# CAN.net
KiCad netlist of a schematic drawn in Altium Designer
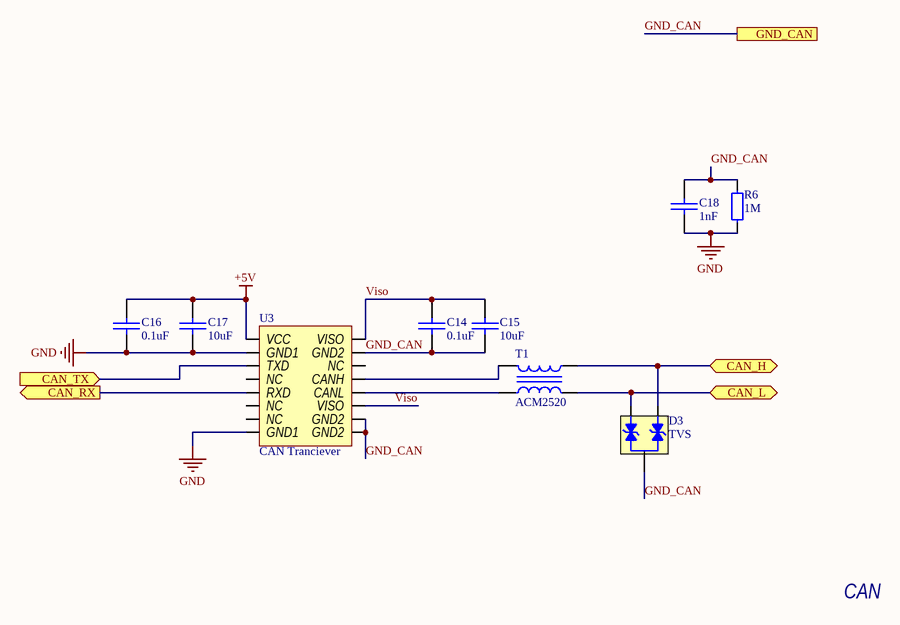
[diagram p0: CAN.SchDoc]

(export (version "E")
  (design (tool "Eeschema 10.0.6"))
  (components
    (comp (ref "C14")
      (value "0.1uF")
      (footprint "0603 Capicator")
      (description "0.1uF X7R 16V 10% 0603")
      (fields
        (field (name "MANUFACTURER") "Murata Manufacturing")
        (field (name "PART NUMBER") "GRM188R71C104KA01D")
      )
      (libsource (lib "ИРА") (part "Cap 0.1uF (0603)"))
    )
    (comp (ref "C15")
      (value "10uF")
      (footprint "0603 Capicator")
      (description "10uF X5R 25V 20% 0603")
      (fields
        (field (name "MANUFACTURER") "Murata Manufacturing")
        (field (name "PART NUMBER") "GRM188R61E106M")
      )
      (libsource (lib "ИРА") (part "Cap 10uF (0603)"))
    )
    (comp (ref "C16")
      (value "0.1uF")
      (footprint "0603 Capicator")
      (description "0.1uF X7R 16V 10% 0603")
      (fields
        (field (name "MANUFACTURER") "Murata Manufacturing")
        (field (name "PART NUMBER") "GRM188R71C104KA01D")
      )
      (libsource (lib "ИРА") (part "Cap 0.1uF (0603)"))
    )
    (comp (ref "C17")
      (value "10uF")
      (footprint "0603 Capicator")
      (description "10uF X5R 25V 20% 0603")
      (fields
        (field (name "MANUFACTURER") "Murata Manufacturing")
        (field (name "PART NUMBER") "GRM188R61E106M")
      )
      (libsource (lib "ИРА") (part "Cap 10uF (0603)"))
    )
    (comp (ref "C18")
      (value "1nF")
      (footprint "0603 Capicator")
      (description "X7R 1nF 100V 10% 0603")
      (fields
        (field (name "MANUFACTURER") "Murata Manufacturing")
        (field (name "PART NUMBER") "GRM188R72A102KA01D")
      )
      (libsource (lib "ИРА") (part "Cap 1nF (0603)"))
    )
    (comp (ref "D3")
      (value "TVS")
      (footprint "SOT-23")
      (fields (field (name "PART NUMBER") "SM24CANB-02HTG") (field (name "MANUFACTURER") "Littelfuse"))
      (libsource (lib "BRT_Components") (part "TVS Diode Arrays"))
    )
    (comp (ref "R6")
      (value "1M")
      (footprint "0603 Resistor")
      (description "0.1W 0603 1M, 1%")
      (fields (field (name "PART NUMBER") "RC0603FR-071ML") (field (name "MANUFACTURER") "Taiwan"))
      (libsource (lib "ИРА") (part "Res 1M (0603)"))
    )
    (comp (ref "T1")
      (value "ACM2520")
      (footprint "ACM2520")
      (description "Common mode filters\r\nAutomotive signal line (for power train/safety)")
      (fields (field (name "MANUFACTURER") "TDK") (field (name "PART NUMBER") "ACM2520-301-2P-T002"))
      (libsource (lib "БУНЭ") (part "ACM2520"))
    )
    (comp (ref "U3")
      (value "CAN Tranciever")
      (footprint "SOIC16W")
      (description "Isolated CAN Tranciever")
      (fields (field (name "MANUFACTURER") "Mornsun Power") (field (name "PART NUMBER") "TDA51SCANHC"))
      (libsource (lib "БУНЭ") (part "TDA51SCANHC"))
    )
  )
  (nets
    (net (code "1") (name "+5V") (class "Default")
      (node (ref "C16") (pin "2") (pinfunction "2_2") (pintype "passive"))
      (node (ref "C17") (pin "2") (pinfunction "2_2") (pintype "passive"))
      (node (ref "U3") (pin "1") (pinfunction "VCC_1") (pintype "passive"))
    )
    (net (code "2") (name "/CAN_H") (class "Default")
      (node (ref "D3") (pin "1") (pinfunction "1_1") (pintype "passive"))
      (node (ref "T1") (pin "2") (pinfunction "2_2") (pintype "passive"))
    )
    (net (code "3") (name "/CAN_L") (class "Default")
      (node (ref "D3") (pin "2") (pinfunction "2_2") (pintype "passive"))
      (node (ref "T1") (pin "4") (pinfunction "4_4") (pintype "passive"))
    )
    (net (code "4") (name "/CAN_RX") (class "Default")
      (node (ref "U3") (pin "5") (pinfunction "RXD_5") (pintype "passive"))
    )
    (net (code "5") (name "/CAN_TX") (class "Default")
      (node (ref "U3") (pin "3") (pinfunction "TXD_3") (pintype "passive"))
    )
    (net (code "6") (name "/GND_CAN") (class "Default")
      (node (ref "C14") (pin "1") (pinfunction "1_1") (pintype "passive"))
      (node (ref "C15") (pin "1") (pinfunction "1_1") (pintype "passive"))
      (node (ref "C18") (pin "2") (pinfunction "2_2") (pintype "passive"))
      (node (ref "D3") (pin "3") (pinfunction "3_3") (pintype "passive"))
      (node (ref "R6") (pin "2") (pinfunction "2_2") (pintype "passive"))
      (node (ref "U3") (pin "10") (pinfunction "GND2_10") (pintype "passive"))
      (node (ref "U3") (pin "15") (pinfunction "GND2_15") (pintype "passive"))
      (node (ref "U3") (pin "9") (pinfunction "GND2_9") (pintype "passive"))
    )
    (net (code "7") (name "/Viso") (class "Default")
      (node (ref "C14") (pin "2") (pinfunction "2_2") (pintype "passive"))
      (node (ref "C15") (pin "2") (pinfunction "2_2") (pintype "passive"))
      (node (ref "U3") (pin "11") (pinfunction "VISO_11") (pintype "passive"))
      (node (ref "U3") (pin "16") (pinfunction "VISO_16") (pintype "passive"))
    )
    (net (code "8") (name "GND") (class "Default")
      (node (ref "C16") (pin "1") (pinfunction "1_1") (pintype "passive"))
      (node (ref "C17") (pin "1") (pinfunction "1_1") (pintype "passive"))
      (node (ref "C18") (pin "1") (pinfunction "1_1") (pintype "passive"))
      (node (ref "R6") (pin "1") (pinfunction "1_1") (pintype "passive"))
      (node (ref "U3") (pin "2") (pinfunction "GND1_2") (pintype "passive"))
      (node (ref "U3") (pin "8") (pinfunction "GND1_8") (pintype "passive"))
    )
    (net (code "9") (name "Net-(U3-CANH)") (class "Default")
      (node (ref "T1") (pin "1") (pinfunction "1_1") (pintype "passive"))
      (node (ref "U3") (pin "13") (pinfunction "CANH_13") (pintype "passive"))
    )
    (net (code "10") (name "Net-(U3-CANL)") (class "Default")
      (node (ref "T1") (pin "3") (pinfunction "3_3") (pintype "passive"))
      (node (ref "U3") (pin "12") (pinfunction "CANL_12") (pintype "passive"))
    )
    (net (code "11") (name "unconnected-(U3-NC-Pad4)") (class "Default")
      (node (ref "U3") (pin "4") (pinfunction "NC_4") (pintype "passive"))
    )
    (net (code "12") (name "unconnected-(U3-NC-Pad6)") (class "Default")
      (node (ref "U3") (pin "6") (pinfunction "NC_6") (pintype "passive"))
    )
    (net (code "13") (name "unconnected-(U3-NC-Pad7)") (class "Default")
      (node (ref "U3") (pin "7") (pinfunction "NC_7") (pintype "passive"))
    )
    (net (code "14") (name "unconnected-(U3-NC-Pad14)") (class "Default")
      (node (ref "U3") (pin "14") (pinfunction "NC_14") (pintype "passive"))
    )
  )
)
